# femtoBeacon_PRO_r3_0_0_single_sided.net
KiCad netlist of a schematic drawn in EAGLE
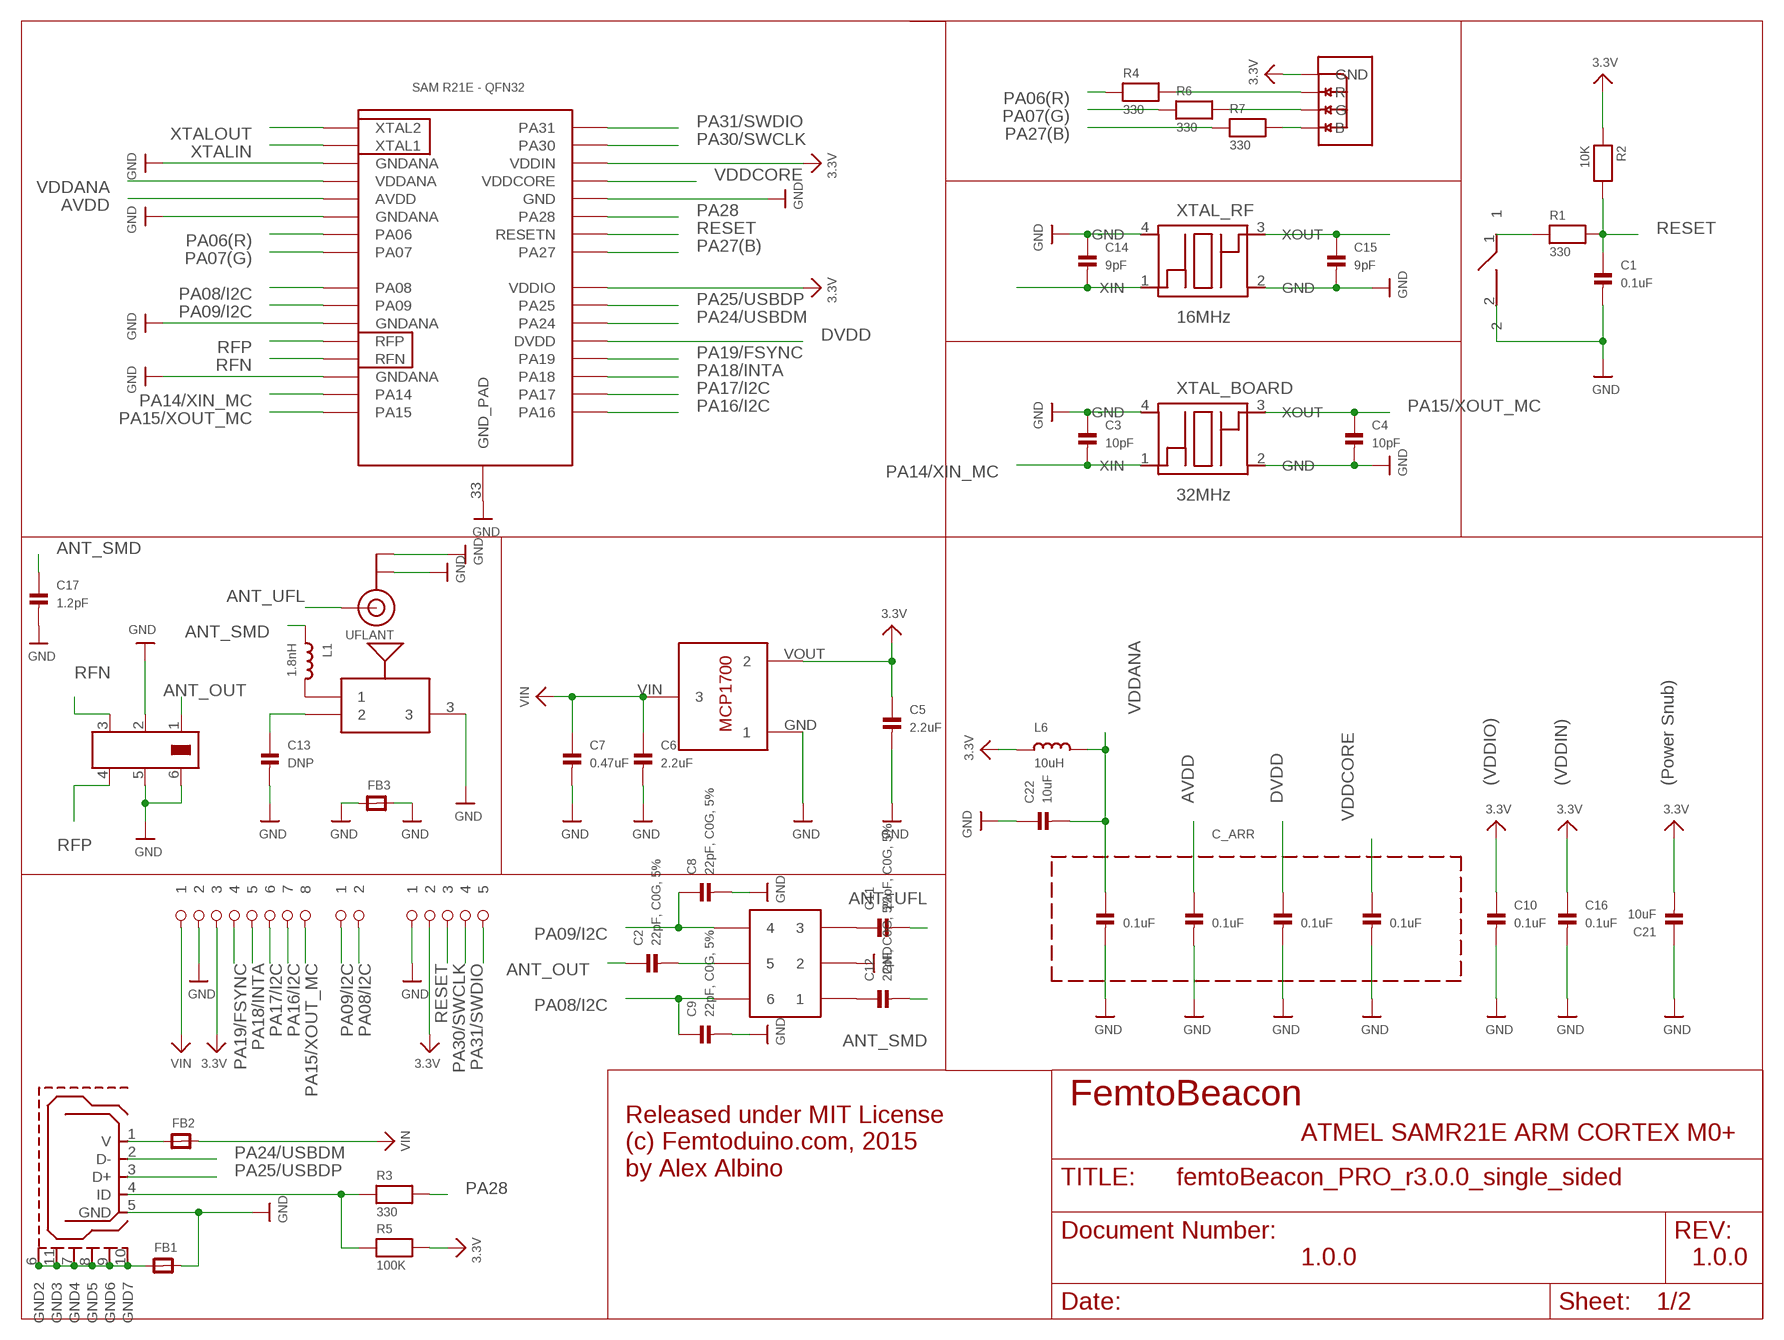
[diagram p0: schematic, sheet 1]
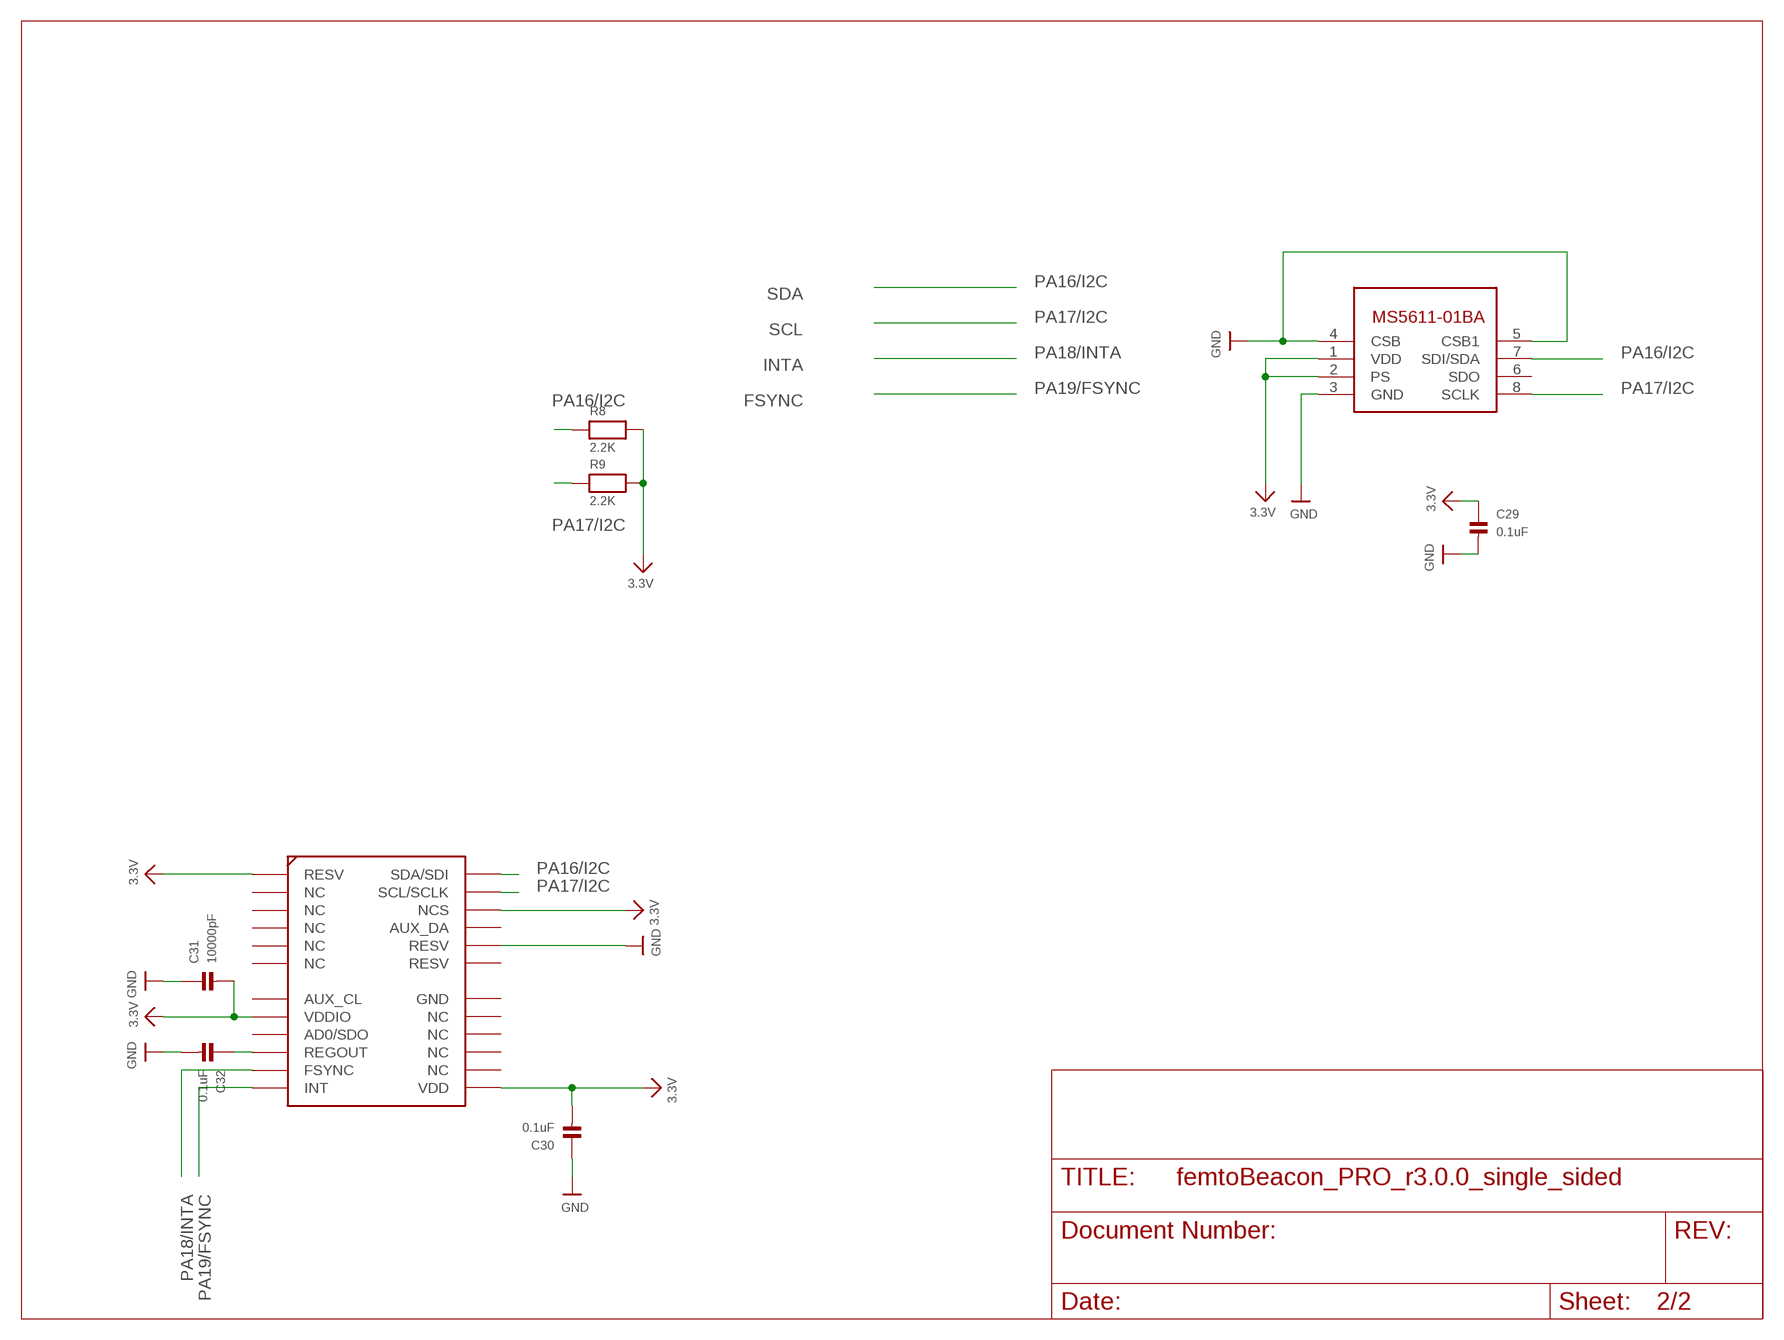
[diagram p1: schematic, sheet 2]

(export (version "E")
  (design (tool "Eeschema 10.0.6"))
  (components
    (comp (ref "BARO")
      (value "MS5611-01BA03")
      (footprint "eagle-import:MS5611-01BA03")
      (libsource (lib "eagle-import") (part "MS5611-01BA03"))
    )
    (comp (ref "C29")
      (value "0.1uF")
      (footprint "eagle-import:_0402MP")
      (fields (field (name "DIGIKEY_PART") "490-3194-1-ND"))
      (libsource (lib "eagle-import") (part "CAP_CERAMIC_0402MP"))
    )
    (comp (ref "C30")
      (value "0.1uF")
      (footprint "eagle-import:_0402MP")
      (fields (field (name "DIGIKEY_PART") "490-3194-1-ND"))
      (libsource (lib "eagle-import") (part "CAP_CERAMIC_0402MP"))
    )
    (comp (ref "C31")
      (value "10000pF")
      (footprint "eagle-import:_0402MP")
      (fields (field (name "DIGIKEY_PART") "490-3194-1-ND"))
      (libsource (lib "eagle-import") (part "CAP_CERAMIC_0402MP"))
    )
    (comp (ref "C32")
      (value "0.1uF")
      (footprint "eagle-import:_0402MP")
      (fields (field (name "DIGIKEY_PART") "490-3194-1-ND"))
      (libsource (lib "eagle-import") (part "CAP_CERAMIC_0402MP"))
    )
    (comp (ref "IMU")
      (value "MPU-9250")
      (footprint "eagle-import:QFN_3X3MM")
      (libsource (lib "eagle-import") (part "MPU-9250"))
    )
    (comp (ref "R8")
      (value "2.2K")
      (footprint "eagle-import:_0402MP")
      (libsource (lib "eagle-import") (part "RESISTOR_0402MP"))
    )
    (comp (ref "R9")
      (value "2.2K")
      (footprint "eagle-import:_0402MP")
      (libsource (lib "eagle-import") (part "RESISTOR_0402MP"))
    )
    (comp (ref "ASWITCH")
      (value "AS222-92LF")
      (footprint "eagle-import:AS222-92LF")
      (libsource (lib "eagle-import") (part "AS222-92LF"))
    )
    (comp (ref "BALUN")
      (value "JOHANSON_2450BM15A0015E")
      (footprint "eagle-import:0805_BALUN")
      (libsource (lib "eagle-import") (part "JOHANSON_2450BM15A0015E"))
    )
    (comp (ref "BTN_RESET")
      (value "DNP")
      (footprint "eagle-import:SPST_SMD")
      (libsource (lib "eagle-import") (part "SPST_SMD"))
    )
    (comp (ref "C1")
      (value "0.1uF")
      (footprint "eagle-import:_0402MP")
      (fields (field (name "DIGIKEY_PART") "490-3194-1-ND"))
      (libsource (lib "eagle-import") (part "CAP_CERAMIC_0402MP"))
    )
    (comp (ref "C2")
      (value "22pF, C0G, 5%")
      (footprint "eagle-import:_0402MP")
      (fields (field (name "DIGIKEY_PART") "490-3194-1-ND"))
      (libsource (lib "eagle-import") (part "CAP_CERAMIC_0402MP"))
    )
    (comp (ref "C3")
      (value "10pF")
      (footprint "eagle-import:_0402MP")
      (fields (field (name "DIGIKEY_PART") "490-3194-1-ND"))
      (libsource (lib "eagle-import") (part "CAP_CERAMIC_0402MP"))
    )
    (comp (ref "C4")
      (value "10pF")
      (footprint "eagle-import:_0402MP")
      (fields (field (name "DIGIKEY_PART") "490-3194-1-ND"))
      (libsource (lib "eagle-import") (part "CAP_CERAMIC_0402MP"))
    )
    (comp (ref "C5")
      (value "2.2uF")
      (footprint "eagle-import:_0402MP")
      (libsource (lib "eagle-import") (part "CAP_CERAMIC_0402MP"))
    )
    (comp (ref "C6")
      (value "2.2uF")
      (footprint "eagle-import:_0402MP")
      (libsource (lib "eagle-import") (part "CAP_CERAMIC_0402MP"))
    )
    (comp (ref "C7")
      (value "0.47uF")
      (footprint "eagle-import:_0402MP")
      (libsource (lib "eagle-import") (part "CAP_CERAMIC_0402MP"))
    )
    (comp (ref "C8")
      (value "22pF, C0G, 5%")
      (footprint "eagle-import:_0402MP")
      (fields (field (name "DIGIKEY_PART") "490-3194-1-ND"))
      (libsource (lib "eagle-import") (part "CAP_CERAMIC_0402MP"))
    )
    (comp (ref "C9")
      (value "22pF, C0G, 5%")
      (footprint "eagle-import:_0402MP")
      (fields (field (name "DIGIKEY_PART") "490-3194-1-ND"))
      (libsource (lib "eagle-import") (part "CAP_CERAMIC_0402MP"))
    )
    (comp (ref "C10")
      (value "0.1uF")
      (footprint "eagle-import:_0402MP")
      (fields (field (name "DIGIKEY_PART") "490-3194-1-ND"))
      (libsource (lib "eagle-import") (part "CAP_CERAMIC_0402MP"))
    )
    (comp (ref "C11")
      (value "22pF, C0G, 5%")
      (footprint "eagle-import:_0402MP")
      (fields (field (name "DIGIKEY_PART") "490-3194-1-ND"))
      (libsource (lib "eagle-import") (part "CAP_CERAMIC_0402MP"))
    )
    (comp (ref "C12")
      (value "22pF, C0G, 5%")
      (footprint "eagle-import:_0402MP")
      (fields (field (name "DIGIKEY_PART") "490-3194-1-ND"))
      (libsource (lib "eagle-import") (part "CAP_CERAMIC_0402MP"))
    )
    (comp (ref "C13")
      (value "DNP")
      (footprint "eagle-import:_0402MP")
      (fields (field (name "DIGIKEY_PART") "490-3194-1-ND"))
      (libsource (lib "eagle-import") (part "CAP_CERAMIC_0402MP"))
    )
    (comp (ref "C14")
      (value "9pF")
      (footprint "eagle-import:_0402MP")
      (fields (field (name "DIGIKEY_PART") "490-3194-1-ND"))
      (libsource (lib "eagle-import") (part "CAP_CERAMIC_0402MP"))
    )
    (comp (ref "C15")
      (value "9pF")
      (footprint "eagle-import:_0402MP")
      (fields (field (name "DIGIKEY_PART") "490-3194-1-ND"))
      (libsource (lib "eagle-import") (part "CAP_CERAMIC_0402MP"))
    )
    (comp (ref "C16")
      (value "0.1uF")
      (footprint "eagle-import:_0402MP")
      (fields (field (name "DIGIKEY_PART") "490-3194-1-ND"))
      (libsource (lib "eagle-import") (part "CAP_CERAMIC_0402MP"))
    )
    (comp (ref "C17")
      (value "1.2pF")
      (footprint "eagle-import:_0402MP")
      (libsource (lib "eagle-import") (part "CAP_CERAMIC_0402MP"))
    )
    (comp (ref "C21")
      (value "10uF")
      (footprint "eagle-import:_0402MP")
      (libsource (lib "eagle-import") (part "CAP_CERAMIC_0402MP"))
    )
    (comp (ref "C22")
      (value "10uF")
      (footprint "eagle-import:_0402MP")
      (libsource (lib "eagle-import") (part "CAP_CERAMIC_0402MP"))
    )
    (comp (ref "C_ARR")
      (value "0.1uF")
      (footprint "eagle-import:CAPACITOR_ARRAY_1206_MONO_1X4")
      (libsource (lib "eagle-import") (part "KEMET_CERAMIC_CAPACITOR_ARRAY_1X4"))
    )
    (comp (ref "FB1")
      (value "FERRITE_0603MP")
      (footprint "eagle-import:_0603MP")
      (libsource (lib "eagle-import") (part "FERRITE_0603MP"))
    )
    (comp (ref "FB2")
      (value "FERRITE_0603MP")
      (footprint "eagle-import:_0603MP")
      (libsource (lib "eagle-import") (part "FERRITE_0603MP"))
    )
    (comp (ref "FB3")
      (value "FERRITE_0603MP")
      (footprint "eagle-import:_0603MP")
      (libsource (lib "eagle-import") (part "FERRITE_0603MP"))
    )
    (comp (ref "IC")
      (value "ATSAMR21E18A-MUT")
      (footprint "eagle-import:QFN32")
      (libsource (lib "eagle-import") (part "ATSAMR21E18A-MUT"))
    )
    (comp (ref "L1")
      (value "1.8nH")
      (footprint "eagle-import:_0603MP")
      (libsource (lib "eagle-import") (part "INDUCTOR_0603MP"))
    )
    (comp (ref "L6")
      (value "10uH")
      (footprint "eagle-import:_0603MP")
      (libsource (lib "eagle-import") (part "INDUCTOR_0603MP"))
    )
    (comp (ref "LDO_VREG")
      (value "MCP1700T-3302E/TT")
      (footprint "eagle-import:MCP1700T-3302E_TT")
      (libsource (lib "eagle-import") (part "MCP1700T-3302E/TT"))
    )
    (comp (ref "R1")
      (value "330")
      (footprint "eagle-import:_0402MP")
      (libsource (lib "eagle-import") (part "RESISTOR_0402MP"))
    )
    (comp (ref "R2")
      (value "10K")
      (footprint "eagle-import:_0402MP")
      (libsource (lib "eagle-import") (part "RESISTOR_0402MP"))
    )
    (comp (ref "R3")
      (value "330")
      (footprint "eagle-import:_0402MP")
      (libsource (lib "eagle-import") (part "RESISTOR_0402MP"))
    )
    (comp (ref "R4")
      (value "330")
      (footprint "eagle-import:_0402MP")
      (libsource (lib "eagle-import") (part "RESISTOR_0402MP"))
    )
    (comp (ref "R5")
      (value "100K")
      (footprint "eagle-import:_0402MP")
      (libsource (lib "eagle-import") (part "RESISTOR_0402MP"))
    )
    (comp (ref "R6")
      (value "330")
      (footprint "eagle-import:_0402MP")
      (libsource (lib "eagle-import") (part "RESISTOR_0402MP"))
    )
    (comp (ref "R7")
      (value "330")
      (footprint "eagle-import:_0402MP")
      (libsource (lib "eagle-import") (part "RESISTOR_0402MP"))
    )
    (comp (ref "RGBLED")
      (value "LRTB_R48G")
      (footprint "eagle-import:LRTB_R48G")
      (libsource (lib "eagle-import") (part "LRTB_R48G"))
    )
    (comp (ref "SMDANT")
      (value "PULSE_ANT_2.4GHZ")
      (footprint "eagle-import:ANT_BAR")
      (libsource (lib "eagle-import") (part "PULSE_ANT_2.4GHZ"))
    )
    (comp (ref "U$5")
      (value "1X8_ROUND")
      (footprint "eagle-import:1X8_ROUND")
      (libsource (lib "eagle-import") (part "1X8_ROUND"))
    )
    (comp (ref "U$9")
      (value "1X2_ROUND")
      (footprint "eagle-import:1X2_ROUND")
      (libsource (lib "eagle-import") (part "1X2_ROUND"))
    )
    (comp (ref "U$10")
      (value "1X5_ROUND")
      (footprint "eagle-import:1X5_ROUND")
      (libsource (lib "eagle-import") (part "1X5_ROUND"))
    )
    (comp (ref "UFLANT")
      (value "ANTENNA_U.FL")
      (footprint "eagle-import:U.FL")
      (libsource (lib "eagle-import") (part "ANTENNA_U.FL"))
    )
    (comp (ref "USB")
      (value "USB_MICROB")
      (footprint "eagle-import:USB_MICROB_PACKAGE")
      (libsource (lib "eagle-import") (part "USB_MICROB"))
    )
    (comp (ref "XTAL_BOARD")
      (value "32MHz")
      (footprint "eagle-import:FA-128")
      (libsource (lib "eagle-import") (part "FA-128"))
    )
    (comp (ref "XTAL_RF")
      (value "16MHz")
      (footprint "eagle-import:TSX-3225")
      (libsource (lib "eagle-import") (part "TSX-3225"))
    )
  )
  (nets
    (net (code "1") (name "3.3V") (class "Default")
      (node (ref "BARO") (pin "1") (pinfunction "VDD_1") (pintype "bidirectional"))
      (node (ref "BARO") (pin "2") (pinfunction "PS_2") (pintype "bidirectional"))
      (node (ref "C10") (pin "1") (pinfunction "P$1_1") (pintype "passive"))
      (node (ref "C16") (pin "1") (pinfunction "P$1_1") (pintype "passive"))
      (node (ref "C21") (pin "2") (pinfunction "P$2_2") (pintype "passive"))
      (node (ref "C29") (pin "1") (pinfunction "P$1_1") (pintype "passive"))
      (node (ref "C30") (pin "2") (pinfunction "P$2_2") (pintype "passive"))
      (node (ref "C31") (pin "2") (pinfunction "P$2_2") (pintype "passive"))
      (node (ref "C5") (pin "1") (pinfunction "P$1_1") (pintype "passive"))
      (node (ref "IC") (pin "24") (pinfunction "VDDIO_24") (pintype "bidirectional"))
      (node (ref "IC") (pin "30") (pinfunction "VDDIN_30") (pintype "bidirectional"))
      (node (ref "IMU") (pin "P$1") (pinfunction "RESV_P$1") (pintype "bidirectional"))
      (node (ref "IMU") (pin "P$13") (pinfunction "VDD_P$13") (pintype "bidirectional"))
      (node (ref "IMU") (pin "P$22") (pinfunction "NCS_P$22") (pintype "bidirectional"))
      (node (ref "IMU") (pin "P$8") (pinfunction "VDDIO_P$8") (pintype "bidirectional"))
      (node (ref "L6") (pin "1") (pinfunction "1_1") (pintype "passive"))
      (node (ref "LDO_VREG") (pin "VOUT") (pinfunction "2_VOUT") (pintype "bidirectional"))
      (node (ref "R2") (pin "1") (pinfunction "1_1") (pintype "passive"))
      (node (ref "R5") (pin "2") (pinfunction "2_2") (pintype "passive"))
      (node (ref "R8") (pin "2") (pinfunction "2_2") (pintype "passive"))
      (node (ref "R9") (pin "2") (pinfunction "2_2") (pintype "passive"))
      (node (ref "RGBLED") (pin "1") (pinfunction "GND_1") (pintype "bidirectional"))
      (node (ref "U$10") (pin "P$2") (pinfunction "2_P$2") (pintype "bidirectional"))
      (node (ref "U$5") (pin "P$3") (pinfunction "3_P$3") (pintype "bidirectional"))
    )
    (net (code "2") (name "ANT_OUT") (class "Default")
      (node (ref "BALUN") (pin "1") (pinfunction "1_1") (pintype "bidirectional"))
      (node (ref "C2") (pin "1") (pinfunction "P$1_1") (pintype "passive"))
    )
    (net (code "3") (name "ANT_SMD") (class "Default")
      (node (ref "C12") (pin "2") (pinfunction "P$2_2") (pintype "passive"))
      (node (ref "C17") (pin "1") (pinfunction "P$1_1") (pintype "passive"))
      (node (ref "L1") (pin "1") (pinfunction "1_1") (pintype "passive"))
    )
    (net (code "4") (name "ANT_UFL") (class "Default")
      (node (ref "C11") (pin "2") (pinfunction "P$2_2") (pintype "passive"))
      (node (ref "UFLANT") (pin "3") (pinfunction "SIGNAL_3") (pintype "passive"))
    )
    (net (code "5") (name "AVDD") (class "Default")
      (node (ref "C_ARR") (pin "3") (pinfunction "P$3_3") (pintype "passive"))
      (node (ref "IC") (pin "5") (pinfunction "AVDD_5") (pintype "bidirectional"))
    )
    (net (code "6") (name "DVDD") (class "Default")
      (node (ref "C_ARR") (pin "5") (pinfunction "P$5_5") (pintype "passive"))
      (node (ref "IC") (pin "21") (pinfunction "DVDD_21") (pintype "bidirectional"))
    )
    (net (code "7") (name "GND") (class "Default")
      (node (ref "ASWITCH") (pin "PIN2") (pinfunction "2_PIN2") (pintype "bidirectional"))
      (node (ref "BALUN") (pin "2") (pinfunction "2_2") (pintype "bidirectional"))
      (node (ref "BALUN") (pin "5") (pinfunction "5_5") (pintype "bidirectional"))
      (node (ref "BALUN") (pin "6") (pinfunction "6_6") (pintype "bidirectional"))
      (node (ref "BARO") (pin "3") (pinfunction "GND_3") (pintype "bidirectional"))
      (node (ref "BARO") (pin "4") (pinfunction "CSB_4") (pintype "bidirectional"))
      (node (ref "BARO") (pin "5") (pinfunction "CSB1_5") (pintype "bidirectional"))
      (node (ref "BTN_RESET") (pin "2") (pinfunction "2_2") (pintype "bidirectional"))
      (node (ref "C1") (pin "2") (pinfunction "P$2_2") (pintype "passive"))
      (node (ref "C10") (pin "2") (pinfunction "P$2_2") (pintype "passive"))
      (node (ref "C13") (pin "2") (pinfunction "P$2_2") (pintype "passive"))
      (node (ref "C14") (pin "1") (pinfunction "P$1_1") (pintype "passive"))
      (node (ref "C15") (pin "2") (pinfunction "P$2_2") (pintype "passive"))
      (node (ref "C16") (pin "2") (pinfunction "P$2_2") (pintype "passive"))
      (node (ref "C17") (pin "2") (pinfunction "P$2_2") (pintype "passive"))
      (node (ref "C21") (pin "1") (pinfunction "P$1_1") (pintype "passive"))
      (node (ref "C22") (pin "1") (pinfunction "P$1_1") (pintype "passive"))
      (node (ref "C29") (pin "2") (pinfunction "P$2_2") (pintype "passive"))
      (node (ref "C3") (pin "1") (pinfunction "P$1_1") (pintype "passive"))
      (node (ref "C30") (pin "1") (pinfunction "P$1_1") (pintype "passive"))
      (node (ref "C31") (pin "1") (pinfunction "P$1_1") (pintype "passive"))
      (node (ref "C32") (pin "2") (pinfunction "P$2_2") (pintype "passive"))
      (node (ref "C4") (pin "2") (pinfunction "P$2_2") (pintype "passive"))
      (node (ref "C5") (pin "2") (pinfunction "P$2_2") (pintype "passive"))
      (node (ref "C6") (pin "2") (pinfunction "P$2_2") (pintype "passive"))
      (node (ref "C7") (pin "2") (pinfunction "P$2_2") (pintype "passive"))
      (node (ref "C8") (pin "2") (pinfunction "P$2_2") (pintype "passive"))
      (node (ref "C9") (pin "2") (pinfunction "P$2_2") (pintype "passive"))
      (node (ref "C_ARR") (pin "2") (pinfunction "P$2_2") (pintype "passive"))
      (node (ref "C_ARR") (pin "4") (pinfunction "P$4_4") (pintype "passive"))
      (node (ref "C_ARR") (pin "6") (pinfunction "P$6_6") (pintype "passive"))
      (node (ref "C_ARR") (pin "8") (pinfunction "P$8_8") (pintype "passive"))
      (node (ref "FB1") (pin "2") (pinfunction "P$2_2") (pintype "passive"))
      (node (ref "FB3") (pin "1") (pinfunction "P$1_1") (pintype "passive"))
      (node (ref "FB3") (pin "2") (pinfunction "P$2_2") (pintype "passive"))
      (node (ref "IC") (pin "11") (pinfunction "GNDANA_11") (pintype "bidirectional"))
      (node (ref "IC") (pin "14") (pinfunction "GNDANA_14") (pintype "bidirectional"))
      (node (ref "IC") (pin "28") (pinfunction "GND_28") (pintype "bidirectional"))
      (node (ref "IC") (pin "3") (pinfunction "GNDANA_3") (pintype "bidirectional"))
      (node (ref "IC") (pin "33") (pinfunction "GND_PAD_33") (pintype "bidirectional"))
      (node (ref "IC") (pin "6") (pinfunction "GNDANA_6") (pintype "bidirectional"))
      (node (ref "IMU") (pin "P$20") (pinfunction "RESV_P$20") (pintype "bidirectional"))
      (node (ref "LDO_VREG") (pin "GND") (pinfunction "1_GND") (pintype "bidirectional"))
      (node (ref "SMDANT") (pin "3") (pinfunction "3_3") (pintype "bidirectional"))
      (node (ref "U$10") (pin "P$1") (pinfunction "1_P$1") (pintype "bidirectional"))
      (node (ref "U$5") (pin "P$2") (pinfunction "2_P$2") (pintype "bidirectional"))
      (node (ref "UFLANT") (pin "1") (pinfunction "GND_1") (pintype "passive"))
      (node (ref "UFLANT") (pin "2") (pinfunction "GND_2") (pintype "passive"))
      (node (ref "USB") (pin "5") (pinfunction "GND_5") (pintype "bidirectional"))
      (node (ref "XTAL_BOARD") (pin "2") (pinfunction "GND_2") (pintype "bidirectional"))
      (node (ref "XTAL_BOARD") (pin "4") (pinfunction "GND_4") (pintype "bidirectional"))
      (node (ref "XTAL_RF") (pin "2") (pinfunction "GND_2") (pintype "bidirectional"))
      (node (ref "XTAL_RF") (pin "4") (pinfunction "GND_4") (pintype "bidirectional"))
    )
    (net (code "8") (name "Net-(ASWITCH-1)") (class "Default")
      (node (ref "ASWITCH") (pin "PIN1") (pinfunction "1_PIN1") (pintype "bidirectional"))
      (node (ref "C12") (pin "1") (pinfunction "P$1_1") (pintype "passive"))
    )
    (net (code "9") (name "Net-(ASWITCH-3)") (class "Default")
      (node (ref "ASWITCH") (pin "PIN3") (pinfunction "3_PIN3") (pintype "bidirectional"))
      (node (ref "C11") (pin "1") (pinfunction "P$1_1") (pintype "passive"))
    )
    (net (code "10") (name "Net-(ASWITCH-5)") (class "Default")
      (node (ref "ASWITCH") (pin "PIN5") (pinfunction "5_PIN5") (pintype "bidirectional"))
      (node (ref "C2") (pin "2") (pinfunction "P$2_2") (pintype "passive"))
    )
    (net (code "11") (name "Net-(BTN_RESET-Pad1)") (class "Default")
      (node (ref "BTN_RESET") (pin "1") (pinfunction "1_1") (pintype "bidirectional"))
      (node (ref "R1") (pin "1") (pinfunction "1_1") (pintype "passive"))
    )
    (net (code "12") (name "Net-(C13-P$1)") (class "Default")
      (node (ref "C13") (pin "1") (pinfunction "P$1_1") (pintype "passive"))
      (node (ref "SMDANT") (pin "2") (pinfunction "2_2") (pintype "bidirectional"))
    )
    (net (code "13") (name "Net-(C32-P$1)") (class "Default")
      (node (ref "C32") (pin "1") (pinfunction "P$1_1") (pintype "passive"))
      (node (ref "IMU") (pin "P$10") (pinfunction "REGOUT_P$10") (pintype "bidirectional"))
    )
    (net (code "14") (name "Net-(FB1-P$1)") (class "Default")
      (node (ref "FB1") (pin "1") (pinfunction "P$1_1") (pintype "passive"))
      (node (ref "USB") (pin "10") (pinfunction "GND7_10") (pintype "bidirectional"))
      (node (ref "USB") (pin "11") (pinfunction "GND3_11") (pintype "bidirectional"))
      (node (ref "USB") (pin "6") (pinfunction "GND2_6") (pintype "bidirectional"))
      (node (ref "USB") (pin "7") (pinfunction "GND4_7") (pintype "bidirectional"))
      (node (ref "USB") (pin "8") (pinfunction "GND5_8") (pintype "bidirectional"))
      (node (ref "USB") (pin "9") (pinfunction "GND6_9") (pintype "bidirectional"))
    )
    (net (code "15") (name "Net-(FB2-P$1)") (class "Default")
      (node (ref "FB2") (pin "1") (pinfunction "P$1_1") (pintype "passive"))
      (node (ref "USB") (pin "1") (pinfunction "V_1") (pintype "bidirectional"))
    )
    (net (code "16") (name "Net-(L1-Pad2)") (class "Default")
      (node (ref "L1") (pin "2") (pinfunction "2_2") (pintype "passive"))
      (node (ref "SMDANT") (pin "1") (pinfunction "1_1") (pintype "bidirectional"))
    )
    (net (code "17") (name "Net-(RGBLED-B)") (class "Default")
      (node (ref "R7") (pin "2") (pinfunction "2_2") (pintype "passive"))
      (node (ref "RGBLED") (pin "4") (pinfunction "B_4") (pintype "bidirectional"))
    )
    (net (code "18") (name "Net-(RGBLED-G)") (class "Default")
      (node (ref "R6") (pin "2") (pinfunction "2_2") (pintype "passive"))
      (node (ref "RGBLED") (pin "3") (pinfunction "G_3") (pintype "bidirectional"))
    )
    (net (code "19") (name "Net-(RGBLED-R)") (class "Default")
      (node (ref "R4") (pin "2") (pinfunction "2_2") (pintype "passive"))
      (node (ref "RGBLED") (pin "2") (pinfunction "R_2") (pintype "bidirectional"))
    )
    (net (code "20") (name "Net-(USB-ID)") (class "Default")
      (node (ref "R3") (pin "1") (pinfunction "1_1") (pintype "passive"))
      (node (ref "R5") (pin "1") (pinfunction "1_1") (pintype "passive"))
      (node (ref "USB") (pin "4") (pinfunction "ID_4") (pintype "bidirectional"))
    )
    (net (code "21") (name "PA06(R)") (class "Default")
      (node (ref "IC") (pin "7") (pinfunction "PA06_7") (pintype "bidirectional"))
      (node (ref "R4") (pin "1") (pinfunction "1_1") (pintype "passive"))
    )
    (net (code "22") (name "PA07(G)") (class "Default")
      (node (ref "IC") (pin "8") (pinfunction "PA07_8") (pintype "bidirectional"))
      (node (ref "R6") (pin "1") (pinfunction "1_1") (pintype "passive"))
    )
    (net (code "23") (name "PA08{slash}I2C") (class "Default")
      (node (ref "ASWITCH") (pin "PIN6") (pinfunction "6_PIN6") (pintype "bidirectional"))
      (node (ref "C9") (pin "1") (pinfunction "P$1_1") (pintype "passive"))
      (node (ref "IC") (pin "9") (pinfunction "PA08_9") (pintype "bidirectional"))
      (node (ref "U$9") (pin "P$2") (pinfunction "2_P$2") (pintype "bidirectional"))
    )
    (net (code "24") (name "PA09{slash}I2C") (class "Default")
      (node (ref "ASWITCH") (pin "PIN4") (pinfunction "4_PIN4") (pintype "bidirectional"))
      (node (ref "C8") (pin "1") (pinfunction "P$1_1") (pintype "passive"))
      (node (ref "IC") (pin "10") (pinfunction "PA09_10") (pintype "bidirectional"))
      (node (ref "U$9") (pin "P$1") (pinfunction "1_P$1") (pintype "bidirectional"))
    )
    (net (code "25") (name "PA14{slash}XIN_MC") (class "Default")
      (node (ref "C3") (pin "2") (pinfunction "P$2_2") (pintype "passive"))
      (node (ref "IC") (pin "15") (pinfunction "PA14_15") (pintype "bidirectional"))
      (node (ref "XTAL_BOARD") (pin "1") (pinfunction "XIN_1") (pintype "bidirectional"))
    )
    (net (code "26") (name "PA15{slash}XOUT_MC") (class "Default")
      (node (ref "C4") (pin "1") (pinfunction "P$1_1") (pintype "passive"))
      (node (ref "IC") (pin "16") (pinfunction "PA15_16") (pintype "bidirectional"))
      (node (ref "U$5") (pin "P$8") (pinfunction "8_P$8") (pintype "bidirectional"))
      (node (ref "XTAL_BOARD") (pin "3") (pinfunction "XOUT_3") (pintype "bidirectional"))
    )
    (net (code "27") (name "PA16{slash}I2C") (class "Default")
      (node (ref "BARO") (pin "7") (pinfunction "SDI/SDA_7") (pintype "bidirectional"))
      (node (ref "IC") (pin "17") (pinfunction "PA16_17") (pintype "bidirectional"))
      (node (ref "IMU") (pin "P$24") (pinfunction "SDA/SDI_P$24") (pintype "bidirectional"))
      (node (ref "R8") (pin "1") (pinfunction "1_1") (pintype "passive"))
      (node (ref "U$5") (pin "P$7") (pinfunction "7_P$7") (pintype "bidirectional"))
    )
    (net (code "28") (name "PA17{slash}I2C") (class "Default")
      (node (ref "BARO") (pin "8") (pinfunction "SCLK_8") (pintype "bidirectional"))
      (node (ref "IC") (pin "18") (pinfunction "PA17_18") (pintype "bidirectional"))
      (node (ref "IMU") (pin "P$23") (pinfunction "SCL/SCLK_P$23") (pintype "bidirectional"))
      (node (ref "R9") (pin "1") (pinfunction "1_1") (pintype "passive"))
      (node (ref "U$5") (pin "P$6") (pinfunction "6_P$6") (pintype "bidirectional"))
    )
    (net (code "29") (name "PA18{slash}INTA") (class "Default")
      (node (ref "IC") (pin "19") (pinfunction "PA18_19") (pintype "bidirectional"))
      (node (ref "IMU") (pin "P$11") (pinfunction "FSYNC_P$11") (pintype "bidirectional"))
      (node (ref "U$5") (pin "P$5") (pinfunction "5_P$5") (pintype "bidirectional"))
    )
    (net (code "30") (name "PA19{slash}FSYNC") (class "Default")
      (node (ref "IC") (pin "20") (pinfunction "PA19_20") (pintype "bidirectional"))
      (node (ref "IMU") (pin "P$12") (pinfunction "INT_P$12") (pintype "bidirectional"))
      (node (ref "U$5") (pin "P$4") (pinfunction "4_P$4") (pintype "bidirectional"))
    )
    (net (code "31") (name "PA24{slash}USBDM") (class "Default")
      (node (ref "IC") (pin "22") (pinfunction "PA24_22") (pintype "bidirectional"))
      (node (ref "USB") (pin "2") (pinfunction "D-_2") (pintype "bidirectional"))
    )
    (net (code "32") (name "PA25{slash}USBDP") (class "Default")
      (node (ref "IC") (pin "23") (pinfunction "PA25_23") (pintype "bidirectional"))
      (node (ref "USB") (pin "3") (pinfunction "D+_3") (pintype "bidirectional"))
    )
    (net (code "33") (name "PA27(B)") (class "Default")
      (node (ref "IC") (pin "25") (pinfunction "PA27_25") (pintype "bidirectional"))
      (node (ref "R7") (pin "1") (pinfunction "1_1") (pintype "passive"))
    )
    (net (code "34") (name "PA28") (class "Default")
      (node (ref "IC") (pin "27") (pinfunction "PA28_27") (pintype "bidirectional"))
      (node (ref "R3") (pin "2") (pinfunction "2_2") (pintype "passive"))
    )
    (net (code "35") (name "PA30{slash}SWCLK") (class "Default")
      (node (ref "IC") (pin "31") (pinfunction "PA30_31") (pintype "bidirectional"))
      (node (ref "U$10") (pin "P$4") (pinfunction "4_P$4") (pintype "bidirectional"))
    )
    (net (code "36") (name "PA31{slash}SWDIO") (class "Default")
      (node (ref "IC") (pin "32") (pinfunction "PA31_32") (pintype "bidirectional"))
      (node (ref "U$10") (pin "P$5") (pinfunction "5_P$5") (pintype "bidirectional"))
    )
    (net (code "37") (name "RESET") (class "Default")
      (node (ref "C1") (pin "1") (pinfunction "P$1_1") (pintype "passive"))
      (node (ref "IC") (pin "26") (pinfunction "RESETN_26") (pintype "bidirectional"))
      (node (ref "R1") (pin "2") (pinfunction "2_2") (pintype "passive"))
      (node (ref "R2") (pin "2") (pinfunction "2_2") (pintype "passive"))
      (node (ref "U$10") (pin "P$3") (pinfunction "3_P$3") (pintype "bidirectional"))
    )
    (net (code "38") (name "RFN") (class "Default")
      (node (ref "BALUN") (pin "3") (pinfunction "3_3") (pintype "bidirectional"))
      (node (ref "IC") (pin "13") (pinfunction "RFN_13") (pintype "bidirectional"))
    )
    (net (code "39") (name "RFP") (class "Default")
      (node (ref "BALUN") (pin "4") (pinfunction "4_4") (pintype "bidirectional"))
      (node (ref "IC") (pin "12") (pinfunction "RFP_12") (pintype "bidirectional"))
    )
    (net (code "40") (name "VDDANA") (class "Default")
      (node (ref "C22") (pin "2") (pinfunction "P$2_2") (pintype "passive"))
      (node (ref "C_ARR") (pin "1") (pinfunction "P$1_1") (pintype "passive"))
      (node (ref "IC") (pin "4") (pinfunction "VDDANA_4") (pintype "bidirectional"))
      (node (ref "L6") (pin "2") (pinfunction "2_2") (pintype "passive"))
    )
    (net (code "41") (name "VDDCORE") (class "Default")
      (node (ref "C_ARR") (pin "7") (pinfunction "P$7_7") (pintype "passive"))
      (node (ref "IC") (pin "29") (pinfunction "VDDCORE_29") (pintype "bidirectional"))
    )
    (net (code "42") (name "VIN") (class "Default")
      (node (ref "C6") (pin "1") (pinfunction "P$1_1") (pintype "passive"))
      (node (ref "C7") (pin "1") (pinfunction "P$1_1") (pintype "passive"))
      (node (ref "FB2") (pin "2") (pinfunction "P$2_2") (pintype "passive"))
      (node (ref "LDO_VREG") (pin "VIN") (pinfunction "3_VIN") (pintype "bidirectional"))
      (node (ref "U$5") (pin "P$1") (pinfunction "1_P$1") (pintype "bidirectional"))
    )
    (net (code "43") (name "XTALIN") (class "Default")
      (node (ref "C14") (pin "2") (pinfunction "P$2_2") (pintype "passive"))
      (node (ref "IC") (pin "2") (pinfunction "XTAL1_2") (pintype "bidirectional"))
      (node (ref "XTAL_RF") (pin "1") (pinfunction "XIN_1") (pintype "bidirectional"))
    )
    (net (code "44") (name "XTALOUT") (class "Default")
      (node (ref "C15") (pin "1") (pinfunction "P$1_1") (pintype "passive"))
      (node (ref "IC") (pin "1") (pinfunction "XTAL2_1") (pintype "bidirectional"))
      (node (ref "XTAL_RF") (pin "3") (pinfunction "XOUT_3") (pintype "bidirectional"))
    )
    (net (code "45") (name "unconnected-(BARO-SDO-Pad6)") (class "Default")
      (node (ref "BARO") (pin "6") (pinfunction "SDO_6") (pintype "bidirectional"))
    )
    (net (code "46") (name "unconnected-(IMU-AD0{slash}SDO-PadP$9)") (class "Default")
      (node (ref "IMU") (pin "P$9") (pinfunction "AD0/SDO_P$9") (pintype "bidirectional"))
    )
    (net (code "47") (name "unconnected-(IMU-AUX_CL-PadP$7)") (class "Default")
      (node (ref "IMU") (pin "P$7") (pinfunction "AUX_CL_P$7") (pintype "bidirectional"))
    )
    (net (code "48") (name "unconnected-(IMU-AUX_DA-PadP$21)") (class "Default")
      (node (ref "IMU") (pin "P$21") (pinfunction "AUX_DA_P$21") (pintype "bidirectional"))
    )
    (net (code "49") (name "unconnected-(IMU-GND-PadP$18)") (class "Default")
      (node (ref "IMU") (pin "P$18") (pinfunction "GND_P$18") (pintype "bidirectional"))
    )
    (net (code "50") (name "unconnected-(IMU-NC-PadP$2)") (class "Default")
      (node (ref "IMU") (pin "P$2") (pinfunction "NC_P$2") (pintype "bidirectional"))
    )
    (net (code "51") (name "unconnected-(IMU-NC-PadP$3)") (class "Default")
      (node (ref "IMU") (pin "P$3") (pinfunction "NC_P$3") (pintype "bidirectional"))
    )
    (net (code "52") (name "unconnected-(IMU-NC-PadP$4)") (class "Default")
      (node (ref "IMU") (pin "P$4") (pinfunction "NC_P$4") (pintype "bidirectional"))
    )
    (net (code "53") (name "unconnected-(IMU-NC-PadP$5)") (class "Default")
      (node (ref "IMU") (pin "P$5") (pinfunction "NC_P$5") (pintype "bidirectional"))
    )
    (net (code "54") (name "unconnected-(IMU-NC-PadP$6)") (class "Default")
      (node (ref "IMU") (pin "P$6") (pinfunction "NC_P$6") (pintype "bidirectional"))
    )
    (net (code "55") (name "unconnected-(IMU-NC-PadP$14)") (class "Default")
      (node (ref "IMU") (pin "P$14") (pinfunction "NC_P$14") (pintype "bidirectional"))
    )
    (net (code "56") (name "unconnected-(IMU-NC-PadP$15)") (class "Default")
      (node (ref "IMU") (pin "P$15") (pinfunction "NC_P$15") (pintype "bidirectional"))
    )
    (net (code "57") (name "unconnected-(IMU-NC-PadP$16)") (class "Default")
      (node (ref "IMU") (pin "P$16") (pinfunction "NC_P$16") (pintype "bidirectional"))
    )
    (net (code "58") (name "unconnected-(IMU-NC-PadP$17)") (class "Default")
      (node (ref "IMU") (pin "P$17") (pinfunction "NC_P$17") (pintype "bidirectional"))
    )
    (net (code "59") (name "unconnected-(IMU-RESV-PadP$19)") (class "Default")
      (node (ref "IMU") (pin "P$19") (pinfunction "RESV_P$19") (pintype "bidirectional"))
    )
  )
)
